# RF_Receive.net
KiCad netlist of a schematic drawn in Altium Designer
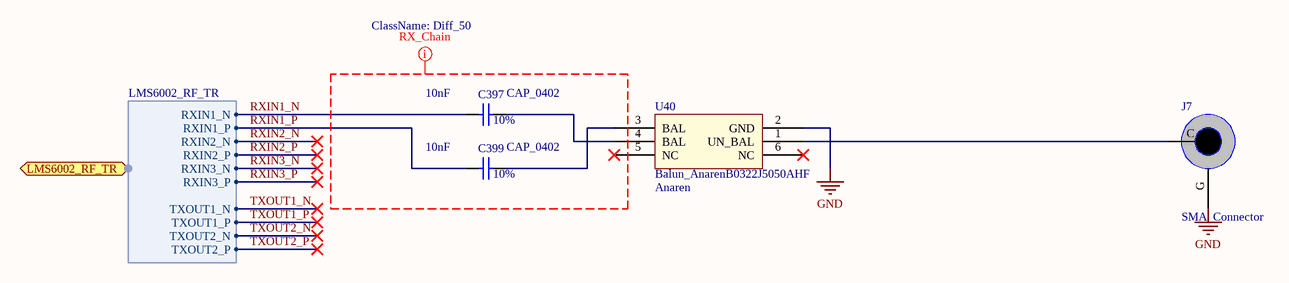
[diagram p0: RF_Receive.SchDoc]

(export (version "E")
  (design (tool "Eeschema 10.0.6"))
  (components
    (comp (ref "C397")
      (value "CAP_0402")
      (footprint "CAPC0402(1005)60_N")
      (description "CAP 10nF, 16V, 10%, EIA 0402")
      (fields
        (field (name "ALTIUM_VALUE") "10nF")
        (field (name "TOLERANCE") "10%")
        (field (name "PART NUMBER") "ATC520L-103KT16T")
        (field (name "MANUFACTURER") "ATC")
      )
      (libsource (lib "COMRAD_Database") (part "CAP_0402"))
    )
    (comp (ref "C399")
      (value "CAP_0402")
      (footprint "CAPC0402(1005)60_N")
      (description "CAP 10nF, 16V, 10%, EIA 0402")
      (fields
        (field (name "ALTIUM_VALUE") "10nF")
        (field (name "TOLERANCE") "10%")
        (field (name "PART NUMBER") "ATC520L-103KT16T")
        (field (name "MANUFACTURER") "ATC")
      )
      (libsource (lib "COMRAD_Database") (part "CAP_0402"))
    )
    (comp (ref "J7")
      (value "SMA_Connector")
      (footprint "Connector_SMA_Amphenol_132255_Edgemount")
      (description "CONN RCPT SMA END LAUNCH PCB")
      (fields (field (name "PART NUMBER") "132255") (field (name "MANUFACTURER") "Amphenol Connex"))
      (libsource (lib "COMRAD_Database") (part "SMA_Connector"))
    )
    (comp (ref "U40")
      (value "Balun_AnarenB0322J5050AHF")
      (footprint "Balun_AnarenB0322J5050AHF_6-PIN_SMD")
      (description "Ultra Low Profile 0805 Balun, 50 ohm unbalanced to 50  Balanced")
      (fields (field (name "PART NUMBER") "B0322J5050AHF") (field (name "MANUFACTURER") "Anaren"))
      (libsource (lib "COMRAD_Database") (part "Balun_AnarenB0322J5050AHF"))
    )
  )
  (nets
    (net (code "2") (name "/RXIN1_N") (class "Default")
      (node (ref "C397") (pin "1") (pinfunction "1_1") (pintype "passive"))
    )
    (net (code "3") (name "/RXIN1_P") (class "Default")
      (node (ref "C399") (pin "1") (pinfunction "1_1") (pintype "passive"))
    )
    (net (code "13") (name "GND") (class "Default")
      (node (ref "J7") (pin "G") (pinfunction "2_G") (pintype "passive"))
      (node (ref "U40") (pin "2") (pinfunction "GND_2") (pintype "passive"))
    )
    (net (code "14") (name "Net-(C397-Pad2)") (class "Default")
      (node (ref "C397") (pin "2") (pinfunction "2_2") (pintype "passive"))
      (node (ref "U40") (pin "4") (pinfunction "BAL_4") (pintype "passive"))
    )
    (net (code "15") (name "Net-(C399-Pad2)") (class "Default")
      (node (ref "C399") (pin "2") (pinfunction "2_2") (pintype "passive"))
      (node (ref "U40") (pin "3") (pinfunction "BAL_3") (pintype "passive"))
    )
    (net (code "16") (name "Net-(J7-1)") (class "Default")
      (node (ref "J7") (pin "C") (pinfunction "1_C") (pintype "passive"))
      (node (ref "U40") (pin "1") (pinfunction "UN_BAL_1") (pintype "passive"))
    )
    (net (code "17") (name "unconnected-(U40-NC-Pad5)") (class "Default")
      (node (ref "U40") (pin "5") (pinfunction "NC_5") (pintype "passive+no_connect"))
    )
    (net (code "18") (name "unconnected-(U40-NC-Pad6)") (class "Default")
      (node (ref "U40") (pin "6") (pinfunction "NC_6") (pintype "passive+no_connect"))
    )
  )
)
